# EEPROM.net
KiCad netlist of a schematic drawn in Altium Designer
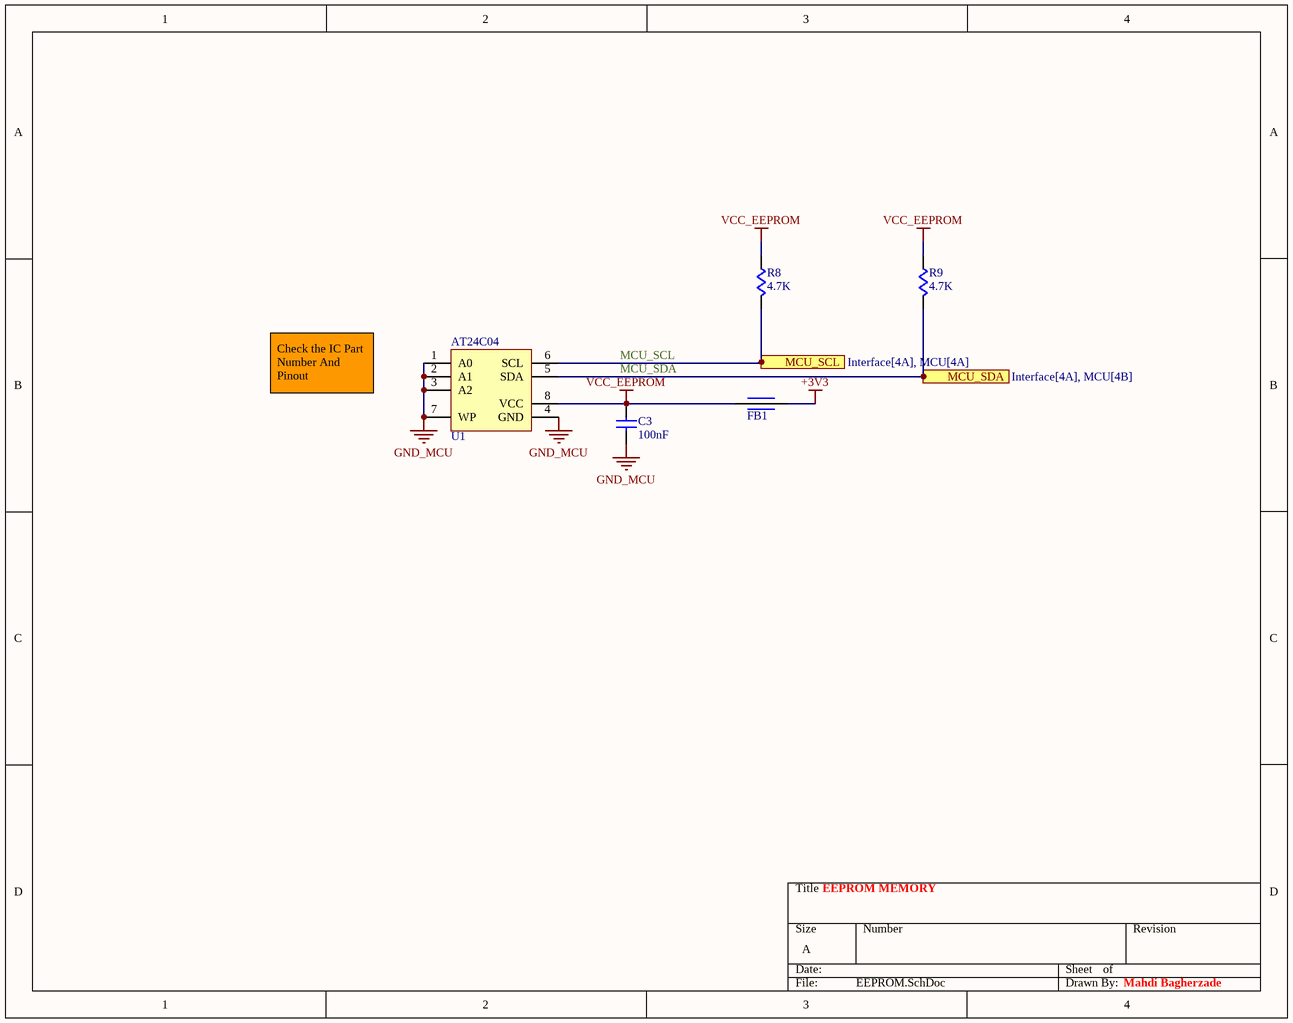
[diagram p0: EEPROM.SchDoc]

(export (version "E")
  (design (tool "Eeschema 10.0.6"))
  (components
    (comp (ref "C3")
      (value "100nF")
      (footprint "C-0805")
      (description "CAPACITOR")
      (fields
        (field (name "VOLTAGE") "50V")
        (field (name "TOLERANCE") "X7R")
        (field (name "PUBLISHER") "Mahdi Bagherzadeh")
      )
      (libsource (lib "Mahdi-Bagherzadeh") (part "CAP-CER"))
    )
    (comp (ref "FB1")
      (value "Ferrite Bead SMD")
      (footprint "FB-0805")
      (description "INDUCATOR")
      (fields (field (name "PUBLISHER") "Mahdi Bagherzadeh"))
      (libsource (lib "Mahdi-Bagherzadeh") (part "FERRITE BEAD"))
    )
    (comp (ref "R8")
      (value "4.7K")
      (footprint "R-0805")
      (description "RESISTOR")
      (fields
        (field (name "POWER") "1/8W")
        (field (name "TOLERANCE") "5%")
        (field (name "PUBLISHER") "Mahdi Bagherzadeh")
      )
      (libsource (lib "Mahdi-Bagherzadeh") (part "RES"))
    )
    (comp (ref "R9")
      (value "4.7K")
      (footprint "R-0805")
      (description "RESISTOR")
      (fields
        (field (name "POWER") "1/8W")
        (field (name "TOLERANCE") "5%")
        (field (name "PUBLISHER") "Mahdi Bagherzadeh")
      )
      (libsource (lib "Mahdi-Bagherzadeh") (part "RES"))
    )
    (comp (ref "U1")
      (value "IC AT24C04-SMD")
      (footprint "SOIC8")
      (description "IC")
      (fields (field (name "CODE") "AT24C04") (field (name "PUBLISHER") "Mahdi Bagherzadeh"))
      (libsource (lib "Mahdi-Bagherzadeh") (part "AT24C04"))
    )
  )
  (nets
    (net (code "1") (name "+3V3") (class "Default")
      (node (ref "FB1") (pin "2") (pinfunction "2_2") (pintype "passive"))
    )
    (net (code "2") (name "/MCU_SCL") (class "Default")
      (node (ref "R8") (pin "2") (pinfunction "2_2") (pintype "passive"))
      (node (ref "U1") (pin "6") (pinfunction "SCL_6") (pintype "passive"))
    )
    (net (code "3") (name "/MCU_SDA") (class "Default")
      (node (ref "R9") (pin "2") (pinfunction "2_2") (pintype "passive"))
      (node (ref "U1") (pin "5") (pinfunction "SDA_5") (pintype "passive"))
    )
    (net (code "4") (name "GND_MCU") (class "Default")
      (node (ref "C3") (pin "2") (pinfunction "2_2") (pintype "passive"))
      (node (ref "U1") (pin "1") (pinfunction "A0_1") (pintype "passive"))
      (node (ref "U1") (pin "2") (pinfunction "A1_2") (pintype "passive"))
      (node (ref "U1") (pin "3") (pinfunction "A2_3") (pintype "passive"))
      (node (ref "U1") (pin "4") (pinfunction "GND_4") (pintype "passive"))
      (node (ref "U1") (pin "7") (pinfunction "WP_7") (pintype "passive"))
    )
    (net (code "5") (name "VCC_EEPROM") (class "Default")
      (node (ref "C3") (pin "1") (pinfunction "1_1") (pintype "passive"))
      (node (ref "FB1") (pin "1") (pinfunction "1_1") (pintype "passive"))
      (node (ref "R8") (pin "1") (pinfunction "1_1") (pintype "passive"))
      (node (ref "R9") (pin "1") (pinfunction "1_1") (pintype "passive"))
      (node (ref "U1") (pin "8") (pinfunction "VCC_8") (pintype "passive"))
    )
  )
)
